# exercise1.net
KiCad netlist of a schematic drawn in Altium Designer
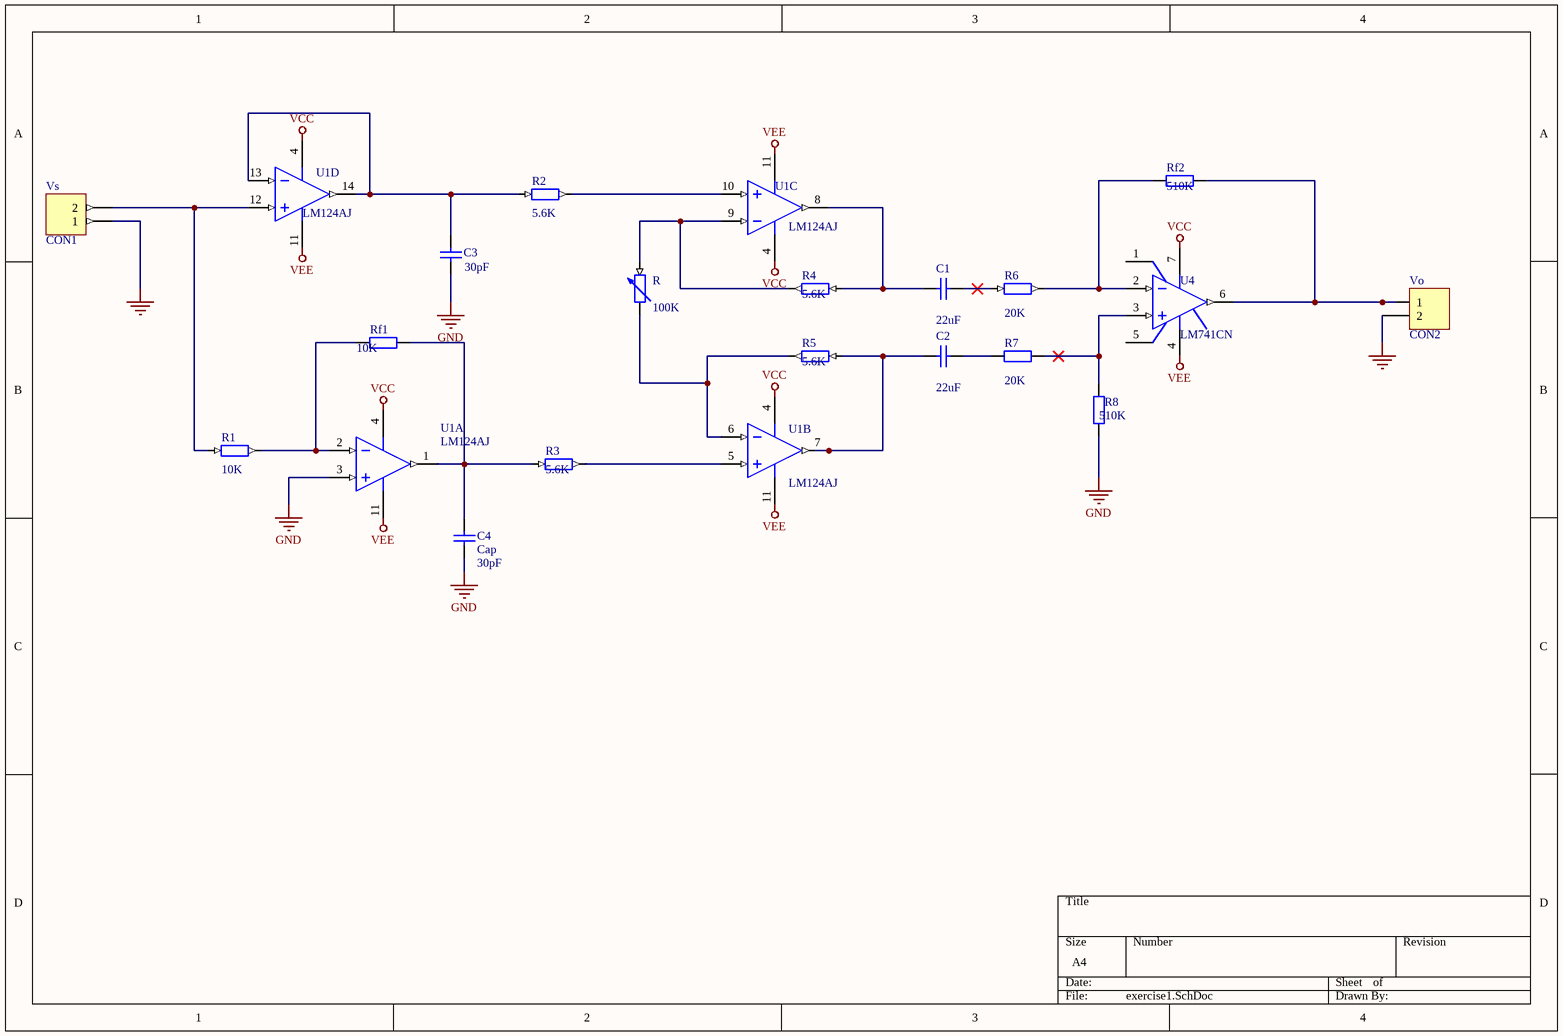
[diagram p0: exercise1.SchDoc]

(export (version "E")
  (design (tool "Eeschema 10.0.6"))
  (components
    (comp (ref "C1")
      (value "22uF")
      (footprint "RAD-0.3")
      (description "Capacitor")
      (fields (field (name "Comment") "Cap") (field (name "PUBLISHER") "Altium Limited"))
      (libsource (lib "Miscellaneous Devices") (part "Cap"))
    )
    (comp (ref "C2")
      (value "22uF")
      (footprint "RAD-0.3")
      (description "Capacitor")
      (fields (field (name "Comment") "Cap") (field (name "PUBLISHER") "Altium Limited"))
      (libsource (lib "Miscellaneous Devices") (part "Cap"))
    )
    (comp (ref "C3")
      (value "30pF")
      (footprint "RAD-0.3")
      (description "Capacitor")
      (fields (field (name "PUBLISHER") "Altium Limited"))
      (libsource (lib "Miscellaneous Devices") (part "Cap"))
    )
    (comp (ref "C4")
      (value "Cap")
      (footprint "RAD-0.3")
      (description "Capacitor")
      (fields (field (name "ALTIUM_VALUE") "30pF") (field (name "PUBLISHER") "Altium Limited"))
      (libsource (lib "Miscellaneous Devices") (part "Cap"))
    )
    (comp (ref "R")
      (value "100K")
      (footprint "AXIAL-0.6")
      (description "Variable Resistor")
      (fields (field (name "Comment") "Res Adj2") (field (name "PUBLISHER") "Altium Limited"))
      (libsource (lib "Miscellaneous Devices") (part "Res Adj2"))
    )
    (comp (ref "R1")
      (value "10K")
      (footprint "AXIAL-0.4")
      (description "Resistor")
      (fields (field (name "Comment") "Res2") (field (name "PUBLISHER") "Altium Limited"))
      (libsource (lib "Miscellaneous Devices") (part "Res2"))
    )
    (comp (ref "R2")
      (value "5.6K")
      (footprint "AXIAL-0.4")
      (description "Resistor")
      (fields (field (name "Comment") "Res2") (field (name "PUBLISHER") "Altium Limited"))
      (libsource (lib "Miscellaneous Devices") (part "Res2"))
    )
    (comp (ref "R3")
      (value "5.6K")
      (footprint "AXIAL-0.4")
      (description "Resistor")
      (fields (field (name "Comment") "Res2") (field (name "PUBLISHER") "Altium Limited"))
      (libsource (lib "Miscellaneous Devices") (part "Res2"))
    )
    (comp (ref "R4")
      (value "5.6K")
      (footprint "AXIAL-0.4")
      (description "Resistor")
      (fields (field (name "Comment") "Res2") (field (name "PUBLISHER") "Altium Limited"))
      (libsource (lib "Miscellaneous Devices") (part "Res2"))
    )
    (comp (ref "R5")
      (value "5.6K")
      (footprint "AXIAL-0.4")
      (description "Resistor")
      (fields (field (name "Comment") "Res2") (field (name "PUBLISHER") "Altium Limited"))
      (libsource (lib "Miscellaneous Devices") (part "Res2"))
    )
    (comp (ref "R6")
      (value "20K")
      (footprint "AXIAL-0.4")
      (description "Resistor")
      (fields (field (name "Comment") "Res2") (field (name "PUBLISHER") "Altium Limited"))
      (libsource (lib "Miscellaneous Devices") (part "Res2"))
    )
    (comp (ref "R7")
      (value "20K")
      (footprint "AXIAL-0.4")
      (description "Resistor")
      (fields (field (name "Comment") "Res2") (field (name "PUBLISHER") "Altium Limited"))
      (libsource (lib "Miscellaneous Devices") (part "Res2"))
    )
    (comp (ref "R8")
      (value "510K")
      (footprint "AXIAL-0.4")
      (description "Resistor")
      (fields (field (name "Comment") "Res2") (field (name "PUBLISHER") "Altium Limited"))
      (libsource (lib "") (part "Res2_1"))
    )
    (comp (ref "Rf1")
      (value "10K")
      (footprint "AXIAL-0.4")
      (description "Resistor")
      (fields (field (name "Comment") "Res2") (field (name "PUBLISHER") "Altium Limited"))
      (libsource (lib "Miscellaneous Devices") (part "Res2"))
    )
    (comp (ref "Rf2")
      (value "510K")
      (footprint "AXIAL-0.4")
      (description "Resistor")
      (fields (field (name "Comment") "Res2") (field (name "PUBLISHER") "Altium Limited"))
      (libsource (lib "Miscellaneous Devices") (part "Res2"))
    )
    (comp (ref "U1")
      (value "LM124AJ")
      (footprint "J14A")
      (description "Low Power Quad Operational Amplifier, 14-pin CerDIP")
      (fields
        (field (name "MANUFACTURER") "National Semiconductor")
        (field (name "PUBLISHER") "Altium Limited")
      )
      (libsource (lib "NSC Amplifier") (part "LM124AJ"))
    )
    (comp (ref "U4")
      (value "LM741CN")
      (footprint "N08E")
      (description "Operational Amplifier, 8-pin MDIP")
      (fields
        (field (name "MANUFACTURER") "National Semiconductor")
        (field (name "PUBLISHER") "Altium Limited")
      )
      (libsource (lib "NSC Amplifier") (part "LM741CN"))
    )
    (comp (ref "Vo")
      (value "CON2")
      (footprint "HDR1X2")
      (description "Header, 2-Pin")
      (fields (field (name "PUBLISHER") "Altium Limited"))
      (libsource (lib "Miscellaneous Connectors") (part "Header 2"))
    )
    (comp (ref "Vs")
      (value "CON1")
      (footprint "HDR1X2")
      (description "Header, 2-Pin")
      (fields (field (name "PUBLISHER") "Altium Limited"))
      (libsource (lib "") (part "Header 2_1"))
    )
  )
  (nets
    (net (code "1") (name "GND") (class "Default")
      (node (ref "C3") (pin "1") (pinfunction "1_1") (pintype "passive"))
      (node (ref "C4") (pin "1") (pinfunction "1_1") (pintype "passive"))
      (node (ref "R8") (pin "1") (pinfunction "1_1") (pintype "passive"))
      (node (ref "U1") (pin "3") (pinfunction "IN1+_3") (pintype "input"))
      (node (ref "Vo") (pin "2") (pinfunction "2_2") (pintype "passive"))
      (node (ref "Vs") (pin "1") (pinfunction "1_1") (pintype "output"))
    )
    (net (code "2") (name "Net-(C1-Pad2)") (class "Default")
      (node (ref "C1") (pin "2") (pinfunction "2_2") (pintype "passive"))
      (node (ref "R6") (pin "1") (pinfunction "1_1") (pintype "input"))
    )
    (net (code "3") (name "Net-(C2-Pad2)") (class "Default")
      (node (ref "C2") (pin "2") (pinfunction "2_2") (pintype "passive"))
      (node (ref "R7") (pin "1") (pinfunction "1_1") (pintype "input"))
    )
    (net (code "4") (name "Net-(U1A-IN1-)") (class "Default")
      (node (ref "R1") (pin "2") (pinfunction "2_2") (pintype "output"))
      (node (ref "Rf1") (pin "1") (pinfunction "1_1") (pintype "input"))
      (node (ref "U1") (pin "2") (pinfunction "IN1-_2") (pintype "input"))
    )
    (net (code "5") (name "Net-(U1A-OUT1)") (class "Default")
      (node (ref "C4") (pin "2") (pinfunction "2_2") (pintype "passive"))
      (node (ref "R3") (pin "1") (pinfunction "1_1") (pintype "input"))
      (node (ref "Rf1") (pin "2") (pinfunction "2_2") (pintype "output"))
      (node (ref "U1") (pin "1") (pinfunction "OUT1_1") (pintype "output"))
    )
    (net (code "6") (name "Net-(U1B-IN2+)") (class "Default")
      (node (ref "R3") (pin "2") (pinfunction "2_2") (pintype "output"))
      (node (ref "U1") (pin "5") (pinfunction "IN2+_5") (pintype "input"))
    )
    (net (code "7") (name "Net-(U1B-IN2-)") (class "Default")
      (node (ref "R") (pin "1") (pinfunction "1_1") (pintype "passive"))
      (node (ref "R5") (pin "1") (pinfunction "1_1") (pintype "input"))
      (node (ref "U1") (pin "6") (pinfunction "IN2-_6") (pintype "input"))
    )
    (net (code "8") (name "Net-(U1B-OUT2)") (class "Default")
      (node (ref "C2") (pin "1") (pinfunction "1_1") (pintype "passive"))
      (node (ref "R5") (pin "2") (pinfunction "2_2") (pintype "output"))
      (node (ref "U1") (pin "7") (pinfunction "OUT2_7") (pintype "output"))
    )
    (net (code "9") (name "Net-(U1C-IN3+)") (class "Default")
      (node (ref "R2") (pin "2") (pinfunction "2_2") (pintype "output"))
      (node (ref "U1") (pin "10") (pinfunction "IN3+_10") (pintype "input"))
    )
    (net (code "10") (name "Net-(U1C-IN3-)") (class "Default")
      (node (ref "R") (pin "2") (pinfunction "2_2") (pintype "input"))
      (node (ref "R4") (pin "1") (pinfunction "1_1") (pintype "input"))
      (node (ref "U1") (pin "9") (pinfunction "IN3-_9") (pintype "input"))
    )
    (net (code "11") (name "Net-(U1C-OUT3)") (class "Default")
      (node (ref "C1") (pin "1") (pinfunction "1_1") (pintype "passive"))
      (node (ref "R4") (pin "2") (pinfunction "2_2") (pintype "output"))
      (node (ref "U1") (pin "8") (pinfunction "OUT3_8") (pintype "output"))
    )
    (net (code "12") (name "Net-(U1D-IN4+)") (class "Default")
      (node (ref "R1") (pin "1") (pinfunction "1_1") (pintype "input"))
      (node (ref "U1") (pin "12") (pinfunction "IN4+_12") (pintype "input"))
      (node (ref "Vs") (pin "2") (pinfunction "2_2") (pintype "output"))
    )
    (net (code "13") (name "Net-(U1D-IN4-)") (class "Default")
      (node (ref "C3") (pin "2") (pinfunction "2_2") (pintype "passive"))
      (node (ref "R2") (pin "1") (pinfunction "1_1") (pintype "input"))
      (node (ref "U1") (pin "13") (pinfunction "IN4-_13") (pintype "input"))
      (node (ref "U1") (pin "14") (pinfunction "OUT4_14") (pintype "output"))
    )
    (net (code "14") (name "Net-(U4-IN+)") (class "Default")
      (node (ref "R7") (pin "2") (pinfunction "2_2") (pintype "output"))
      (node (ref "R8") (pin "2") (pinfunction "2_2") (pintype "passive"))
      (node (ref "U4") (pin "3") (pinfunction "IN+_3") (pintype "input"))
    )
    (net (code "15") (name "Net-(U4-IN-)") (class "Default")
      (node (ref "R6") (pin "2") (pinfunction "2_2") (pintype "output"))
      (node (ref "Rf2") (pin "1") (pinfunction "1_1") (pintype "input"))
      (node (ref "U4") (pin "2") (pinfunction "IN-_2") (pintype "input"))
    )
    (net (code "16") (name "Net-(U4-OUT)") (class "Default")
      (node (ref "Rf2") (pin "2") (pinfunction "2_2") (pintype "output"))
      (node (ref "U4") (pin "6") (pinfunction "OUT_6") (pintype "output"))
      (node (ref "Vo") (pin "1") (pinfunction "1_1") (pintype "passive"))
    )
    (net (code "17") (name "VCC") (class "Default")
      (node (ref "U1") (pin "4") (pinfunction "V+_4") (pintype "power_in"))
      (node (ref "U4") (pin "7") (pinfunction "V+_7") (pintype "power_in"))
    )
    (net (code "18") (name "VEE") (class "Default")
      (node (ref "U1") (pin "11") (pinfunction "GND_11") (pintype "power_in"))
      (node (ref "U4") (pin "4") (pinfunction "V-_4") (pintype "power_in"))
    )
    (net (code "19") (name "unconnected-(U4-NC-Pad8)") (class "Default")
      (node (ref "U4") (pin "8") (pinfunction "NC_8") (pintype "passive"))
    )
    (net (code "20") (name "unconnected-(U4-OFS_NULL-Pad1)") (class "Default")
      (node (ref "U4") (pin "1") (pinfunction "OFS_NULL_1") (pintype "passive"))
    )
    (net (code "21") (name "unconnected-(U4-OFS_NULL-Pad5)") (class "Default")
      (node (ref "U4") (pin "5") (pinfunction "OFS_NULL_5") (pintype "passive"))
    )
  )
)
